# Adapter.net
KiCad netlist of a schematic drawn in Altium Designer
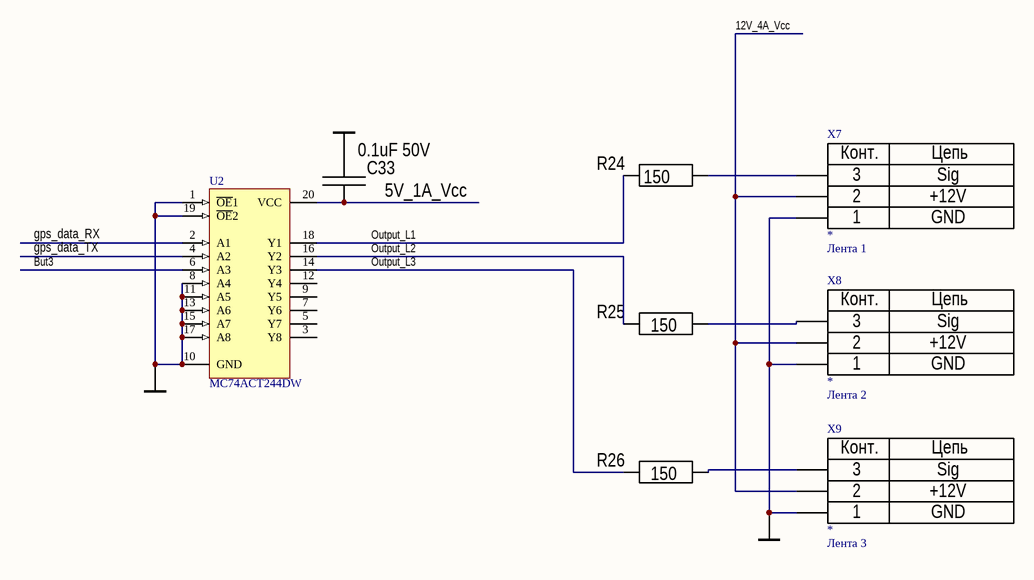
[diagram p0: Adapter.SchDoc]

(export (version "E")
  (design (tool "Eeschema 10.0.6"))
  (components
    (comp (ref "C33")
      (value "0.1uF 50V")
      (footprint "0805_CAP")
      (libsource (lib "Integrated_Library_tikhovikt") (part "Cap_np"))
    )
    (comp (ref "R24")
      (value "150")
      (footprint "0805_RES")
      (libsource (lib "Integrated_Library_tikhovikt") (part "Res"))
    )
    (comp (ref "R25")
      (value "150")
      (footprint "0805_RES")
      (libsource (lib "Integrated_Library_tikhovikt") (part "Res"))
    )
    (comp (ref "R26")
      (value "150")
      (footprint "0805_RES")
      (libsource (lib "Integrated_Library_tikhovikt") (part "Res"))
    )
    (comp (ref "U2")
      (value "MC74ACT244DW")
      (footprint "751D-04_N")
      (description "Octal Buffer/Line Driver with 3-State Outputs")
      (fields (field (name "PUBLISHER") "Altium Limited"))
      (libsource (lib "ON Semi Logic Buffer Line Driver") (part "MC74ACT244DW"))
    )
    (comp (ref "X7")
      (value "*")
      (footprint "3pad_5.08")
      (fields (field (name "DESTINY") "Лента 1"))
      (libsource (lib "Integrated_Library_tikhovikt") (part "3pin_conn"))
    )
    (comp (ref "X8")
      (value "*")
      (footprint "3pad_5.08")
      (fields (field (name "DESTINY") "Лента 2"))
      (libsource (lib "Integrated_Library_tikhovikt") (part "3pin_conn"))
    )
    (comp (ref "X9")
      (value "*")
      (footprint "3pad_5.08")
      (fields (field (name "DESTINY") "Лента 3"))
      (libsource (lib "Integrated_Library_tikhovikt") (part "3pin_conn"))
    )
  )
  (nets
    (net (code "1") (name "/5V_1A_Vcc") (class "Default")
      (node (ref "C33") (pin "1") (pinfunction "1_1") (pintype "passive"))
      (node (ref "U2") (pin "20") (pinfunction "VCC_20") (pintype "power_in"))
    )
    (net (code "2") (name "/12V_4A_Vcc") (class "Default")
      (node (ref "X7") (pin "2") (pinfunction "2_2") (pintype "passive"))
      (node (ref "X8") (pin "2") (pinfunction "2_2") (pintype "passive"))
      (node (ref "X9") (pin "2") (pinfunction "2_2") (pintype "passive"))
    )
    (net (code "3") (name "/But3") (class "Default")
      (node (ref "U2") (pin "6") (pinfunction "A3_6") (pintype "input"))
    )
    (net (code "4") (name "/Output_L1") (class "Default")
      (node (ref "R24") (pin "1") (pinfunction "1_1") (pintype "passive"))
      (node (ref "U2") (pin "18") (pinfunction "Y1_18") (pintype "tri_state"))
    )
    (net (code "5") (name "/Output_L2") (class "Default")
      (node (ref "R25") (pin "1") (pinfunction "1_1") (pintype "passive"))
      (node (ref "U2") (pin "16") (pinfunction "Y2_16") (pintype "tri_state"))
    )
    (net (code "6") (name "/Output_L3") (class "Default")
      (node (ref "R26") (pin "1") (pinfunction "1_1") (pintype "passive"))
      (node (ref "U2") (pin "14") (pinfunction "Y3_14") (pintype "tri_state"))
    )
    (net (code "7") (name "/gps_data_RX") (class "Default")
      (node (ref "U2") (pin "2") (pinfunction "A1_2") (pintype "input"))
    )
    (net (code "8") (name "/gps_data_TX") (class "Default")
      (node (ref "U2") (pin "4") (pinfunction "A2_4") (pintype "input"))
    )
    (net (code "9") (name "GND") (class "Default")
      (node (ref "C33") (pin "2") (pinfunction "2_2") (pintype "passive"))
      (node (ref "U2") (pin "1") (pinfunction "~{OE}1_1") (pintype "input"))
      (node (ref "U2") (pin "10") (pinfunction "GND_10") (pintype "power_in"))
      (node (ref "U2") (pin "11") (pinfunction "A5_11") (pintype "input"))
      (node (ref "U2") (pin "13") (pinfunction "A6_13") (pintype "input"))
      (node (ref "U2") (pin "15") (pinfunction "A7_15") (pintype "input"))
      (node (ref "U2") (pin "17") (pinfunction "A8_17") (pintype "input"))
      (node (ref "U2") (pin "19") (pinfunction "~{OE}2_19") (pintype "input"))
      (node (ref "U2") (pin "8") (pinfunction "A4_8") (pintype "input"))
      (node (ref "X7") (pin "1") (pinfunction "1_1") (pintype "passive"))
      (node (ref "X8") (pin "1") (pinfunction "1_1") (pintype "passive"))
      (node (ref "X9") (pin "1") (pinfunction "1_1") (pintype "passive"))
    )
    (net (code "10") (name "Net-(R24-Pad2)") (class "Default")
      (node (ref "R24") (pin "2") (pinfunction "2_2") (pintype "passive"))
      (node (ref "X7") (pin "3") (pinfunction "3_3") (pintype "passive"))
    )
    (net (code "11") (name "Net-(R25-Pad2)") (class "Default")
      (node (ref "R25") (pin "2") (pinfunction "2_2") (pintype "passive"))
      (node (ref "X8") (pin "3") (pinfunction "3_3") (pintype "passive"))
    )
    (net (code "12") (name "Net-(R26-Pad2)") (class "Default")
      (node (ref "R26") (pin "2") (pinfunction "2_2") (pintype "passive"))
      (node (ref "X9") (pin "3") (pinfunction "3_3") (pintype "passive"))
    )
    (net (code "13") (name "unconnected-(U2-Y4-Pad12)") (class "Default")
      (node (ref "U2") (pin "12") (pinfunction "Y4_12") (pintype "tri_state"))
    )
    (net (code "14") (name "unconnected-(U2-Y5-Pad9)") (class "Default")
      (node (ref "U2") (pin "9") (pinfunction "Y5_9") (pintype "tri_state"))
    )
    (net (code "15") (name "unconnected-(U2-Y6-Pad7)") (class "Default")
      (node (ref "U2") (pin "7") (pinfunction "Y6_7") (pintype "tri_state"))
    )
    (net (code "16") (name "unconnected-(U2-Y7-Pad5)") (class "Default")
      (node (ref "U2") (pin "5") (pinfunction "Y7_5") (pintype "tri_state"))
    )
    (net (code "17") (name "unconnected-(U2-Y8-Pad3)") (class "Default")
      (node (ref "U2") (pin "3") (pinfunction "Y8_3") (pintype "tri_state"))
    )
  )
)
